# 1_ATmega_SoC_schdoc.net
KiCad netlist of a schematic drawn in Altium Designer
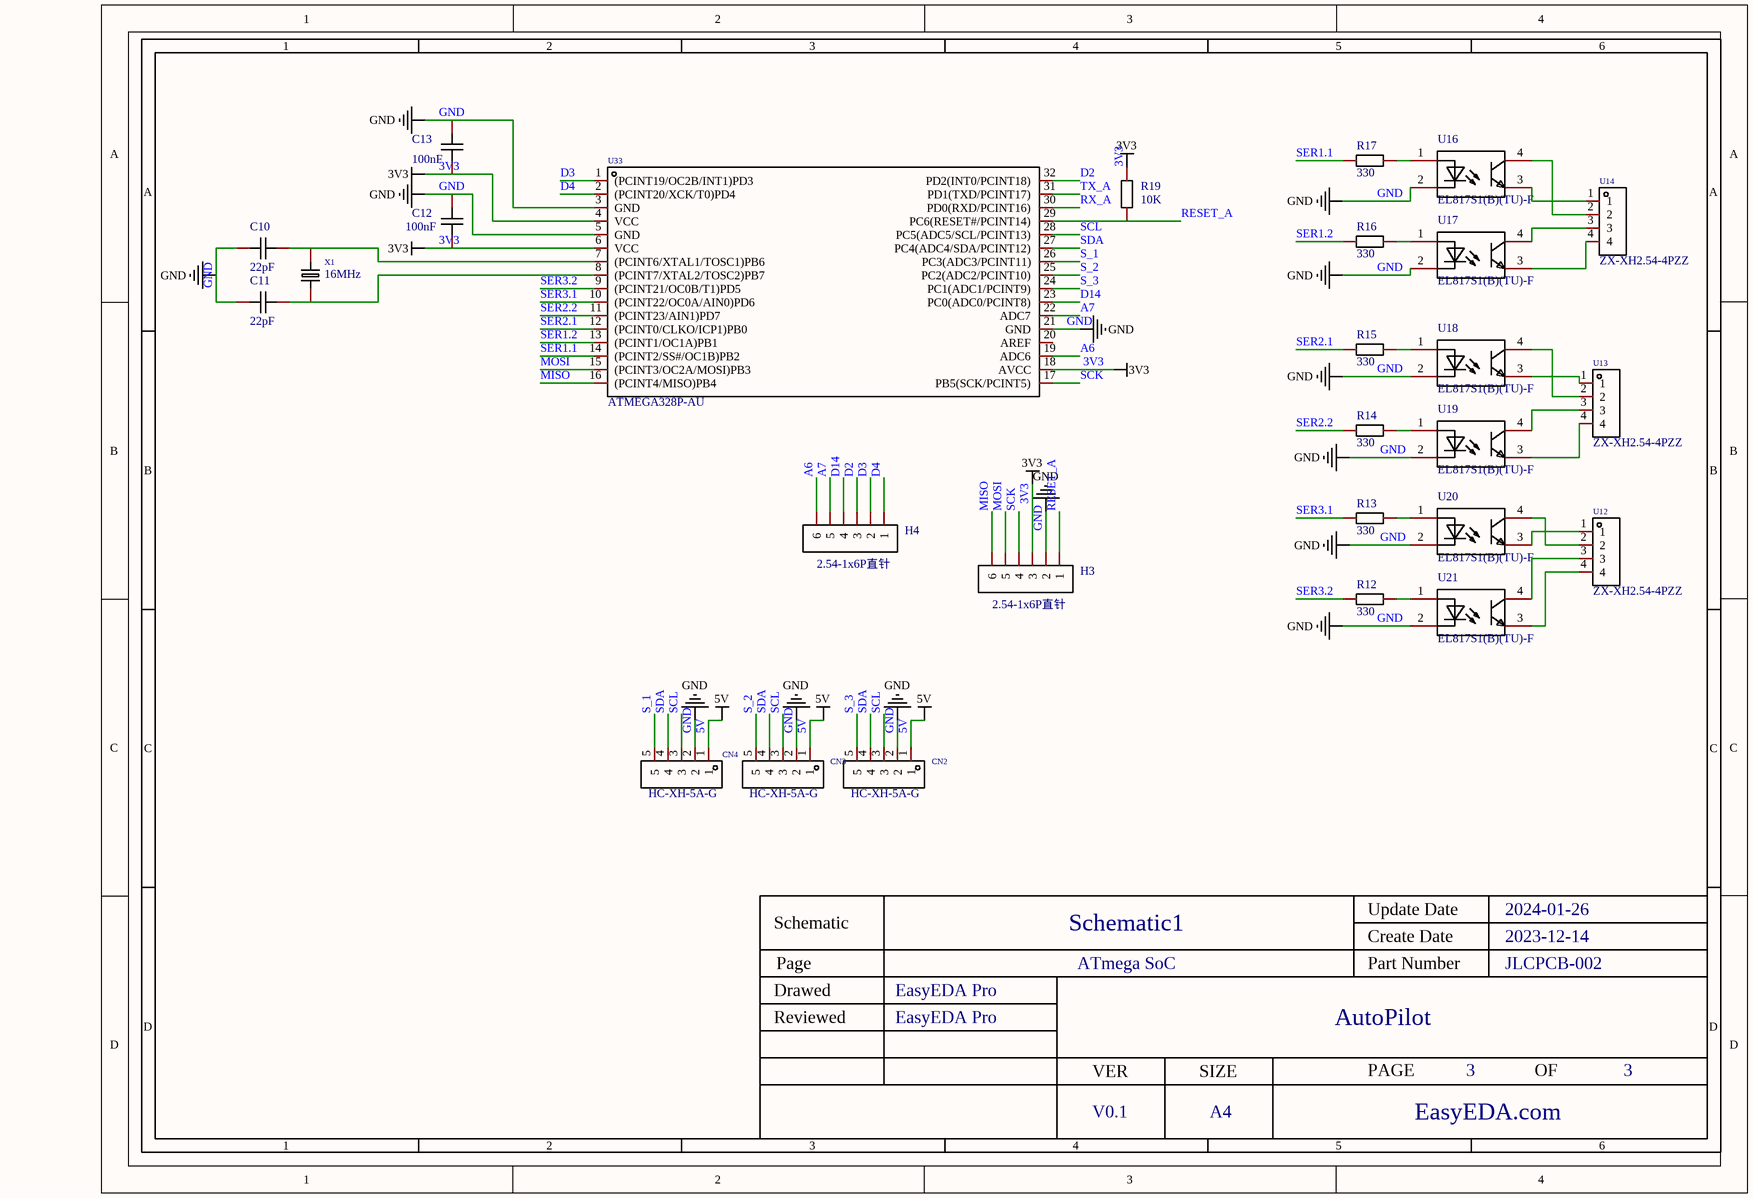
[diagram p0: 1_ATmega SoC.schdoc.schdoc]

(export (version "E")
  (design (tool "Eeschema 10.0.6"))
  (components
    (comp (ref "C10")
      (value "22pF")
      (fields (field (name "NAME") "22pF"))
      (libsource (lib "altium-import") (part "root_0_CAP_0603_"))
    )
    (comp (ref "C11")
      (value "22pF")
      (fields (field (name "NAME") "22pF"))
      (libsource (lib "altium-import") (part "root_0_CAP_0603_"))
    )
    (comp (ref "C12")
      (value "100nF")
      (fields (field (name "NAME") "100nF"))
      (libsource (lib "altium-import") (part "root_1_CAP_0603_"))
    )
    (comp (ref "C13")
      (value "100nF")
      (fields (field (name "NAME") "100nF"))
      (libsource (lib "altium-import") (part "root_1_CAP_0603_"))
    )
    (comp (ref "CN2")
      (value "HC-XH-5A-G")
      (fields (field (name "NAME") "HC-XH-5A-G") (field (name "MANUFACTURER") "HCTL(华灿天禄)"))
      (libsource (lib "altium-import") (part "root_3_HC-XH-5A-G_"))
    )
    (comp (ref "CN3")
      (value "HC-XH-5A-G")
      (fields (field (name "NAME") "HC-XH-5A-G") (field (name "MANUFACTURER") "HCTL(华灿天禄)"))
      (libsource (lib "altium-import") (part "root_3_HC-XH-5A-G_"))
    )
    (comp (ref "CN4")
      (value "HC-XH-5A-G")
      (fields (field (name "NAME") "HC-XH-5A-G") (field (name "MANUFACTURER") "HCTL(华灿天禄)"))
      (libsource (lib "altium-import") (part "root_3_HC-XH-5A-G_"))
    )
    (comp (ref "H3")
      (value "2.54-1x6P直针")
      (fields (field (name "NAME") "2.54-1x6P直针") (field (name "MANUFACTURER") "BOOMELE(博穆精密)"))
      (libsource (lib "altium-import") (part "root_3_2.54-1x6P直针_"))
    )
    (comp (ref "H4")
      (value "2.54-1x6P直针")
      (fields (field (name "NAME") "2.54-1x6P直针") (field (name "MANUFACTURER") "BOOMELE(博穆精密)"))
      (libsource (lib "altium-import") (part "root_3_2.54-1x6P直针_"))
    )
    (comp (ref "R12")
      (value "330")
      (fields (field (name "NAME") "330"))
      (libsource (lib "altium-import") (part "root_0_Res_0603_"))
    )
    (comp (ref "R13")
      (value "330")
      (fields (field (name "NAME") "330"))
      (libsource (lib "altium-import") (part "root_0_Res_0603_"))
    )
    (comp (ref "R14")
      (value "330")
      (fields (field (name "NAME") "330"))
      (libsource (lib "altium-import") (part "root_0_Res_0603_"))
    )
    (comp (ref "R15")
      (value "330")
      (fields (field (name "NAME") "330"))
      (libsource (lib "altium-import") (part "root_0_Res_0603_"))
    )
    (comp (ref "R16")
      (value "330")
      (fields (field (name "NAME") "330"))
      (libsource (lib "altium-import") (part "root_0_Res_0603_"))
    )
    (comp (ref "R17")
      (value "330")
      (fields (field (name "NAME") "330"))
      (libsource (lib "altium-import") (part "root_0_Res_0603_"))
    )
    (comp (ref "R19")
      (value "10K")
      (fields (field (name "NAME") "10K"))
      (libsource (lib "altium-import") (part "root_1_Res_0603_"))
    )
    (comp (ref "U12")
      (value "ZX-XH2.54-4PZZ")
      (fields (field (name "NAME") "ZX-XH2.54-4PZZ") (field (name "MANUFACTURER") "Megastar(兆星)"))
      (libsource (lib "altium-import") (part "root_0_ZX-XH2.54-4PZZ_"))
    )
    (comp (ref "U13")
      (value "ZX-XH2.54-4PZZ")
      (fields (field (name "NAME") "ZX-XH2.54-4PZZ") (field (name "MANUFACTURER") "Megastar(兆星)"))
      (libsource (lib "altium-import") (part "root_0_ZX-XH2.54-4PZZ_"))
    )
    (comp (ref "U14")
      (value "ZX-XH2.54-4PZZ")
      (fields (field (name "NAME") "ZX-XH2.54-4PZZ") (field (name "MANUFACTURER") "Megastar(兆星)"))
      (libsource (lib "altium-import") (part "root_0_ZX-XH2.54-4PZZ_"))
    )
    (comp (ref "U16")
      (value "EL817S1(B)(TU)-F")
      (fields (field (name "NAME") "EL817S1(B)(TU)-F") (field (name "MANUFACTURER") "EVERLIGHT(亿光)"))
      (libsource (lib "altium-import") (part "root_0_EL817S1(B)(TU)-F_"))
    )
    (comp (ref "U17")
      (value "EL817S1(B)(TU)-F")
      (fields (field (name "NAME") "EL817S1(B)(TU)-F") (field (name "MANUFACTURER") "EVERLIGHT(亿光)"))
      (libsource (lib "altium-import") (part "root_0_EL817S1(B)(TU)-F_"))
    )
    (comp (ref "U18")
      (value "EL817S1(B)(TU)-F")
      (fields (field (name "NAME") "EL817S1(B)(TU)-F") (field (name "MANUFACTURER") "EVERLIGHT(亿光)"))
      (libsource (lib "altium-import") (part "root_0_EL817S1(B)(TU)-F_"))
    )
    (comp (ref "U19")
      (value "EL817S1(B)(TU)-F")
      (fields (field (name "NAME") "EL817S1(B)(TU)-F") (field (name "MANUFACTURER") "EVERLIGHT(亿光)"))
      (libsource (lib "altium-import") (part "root_0_EL817S1(B)(TU)-F_"))
    )
    (comp (ref "U20")
      (value "EL817S1(B)(TU)-F")
      (fields (field (name "NAME") "EL817S1(B)(TU)-F") (field (name "MANUFACTURER") "EVERLIGHT(亿光)"))
      (libsource (lib "altium-import") (part "root_0_EL817S1(B)(TU)-F_"))
    )
    (comp (ref "U21")
      (value "EL817S1(B)(TU)-F")
      (fields (field (name "NAME") "EL817S1(B)(TU)-F") (field (name "MANUFACTURER") "EVERLIGHT(亿光)"))
      (libsource (lib "altium-import") (part "root_0_EL817S1(B)(TU)-F_"))
    )
    (comp (ref "U33")
      (value "ATMEGA328P-AU")
      (fields (field (name "NAME") "ATMEGA328P-AU") (field (name "MANUFACTURER") "MICROCHIP(美国微芯)"))
      (libsource (lib "altium-import") (part "root_0_ATMEGA328P-AU_C14877_"))
    )
    (comp (ref "X1")
      (value "16MHz")
      (fields
        (field (name "NAME") "16MHz")
        (field (name "MANUFACTURER") "YJX(雅晶鑫)")
        (field (name "MANUFACTURER PART") "TAXM16M2GLFBET2T")
      )
      (libsource (lib "altium-import") (part "root_1_TAXM16M2GLFBET2T_"))
    )
  )
  (nets
    (net (code "1") (name "/A6") (class "Default")
      (node (ref "H4") (pin "6") (pinfunction "6_6") (pintype "passive"))
      (node (ref "U33") (pin "19") (pinfunction "ADC6_19") (pintype "passive"))
    )
    (net (code "2") (name "/A7") (class "Default")
      (node (ref "H4") (pin "5") (pinfunction "5_5") (pintype "passive"))
      (node (ref "U33") (pin "22") (pinfunction "ADC7_22") (pintype "passive"))
    )
    (net (code "3") (name "/D2") (class "Default")
      (node (ref "H4") (pin "3") (pinfunction "3_3") (pintype "passive"))
      (node (ref "U33") (pin "32") (pinfunction "PD2(INT0/PCINT18)_32") (pintype "passive"))
    )
    (net (code "4") (name "/D3") (class "Default")
      (node (ref "H4") (pin "2") (pinfunction "2_2") (pintype "passive"))
      (node (ref "U33") (pin "1") (pinfunction "(PCINT19/OC2B/INT1)PD3_1") (pintype "passive"))
    )
    (net (code "5") (name "/D4") (class "Default")
      (node (ref "H4") (pin "1") (pinfunction "1_1") (pintype "passive"))
      (node (ref "U33") (pin "2") (pinfunction "(PCINT20/XCK/T0)PD4_2") (pintype "passive"))
    )
    (net (code "6") (name "/D14") (class "Default")
      (node (ref "H4") (pin "4") (pinfunction "4_4") (pintype "passive"))
      (node (ref "U33") (pin "23") (pinfunction "PC0(ADC0/PCINT8)_23") (pintype "passive"))
    )
    (net (code "7") (name "/MISO") (class "Default")
      (node (ref "H3") (pin "6") (pinfunction "6_6") (pintype "passive"))
      (node (ref "U33") (pin "16") (pinfunction "(PCINT4/MISO)PB4_16") (pintype "passive"))
    )
    (net (code "8") (name "/MOSI") (class "Default")
      (node (ref "H3") (pin "5") (pinfunction "5_5") (pintype "passive"))
      (node (ref "U33") (pin "15") (pinfunction "(PCINT3/OC2A/MOSI)PB3_15") (pintype "passive"))
    )
    (net (code "9") (name "/RESET_A") (class "Default")
      (node (ref "H3") (pin "1") (pinfunction "1_1") (pintype "passive"))
      (node (ref "R19") (pin "1") (pinfunction "1_1") (pintype "passive"))
      (node (ref "U33") (pin "29") (pinfunction "PC6(RESET#/PCINT14)_29") (pintype "passive"))
    )
    (net (code "10") (name "/RX_A") (class "Default")
      (node (ref "U33") (pin "30") (pinfunction "PD0(RXD/PCINT16)_30") (pintype "passive"))
    )
    (net (code "11") (name "/SCK") (class "Default")
      (node (ref "H3") (pin "4") (pinfunction "4_4") (pintype "passive"))
      (node (ref "U33") (pin "17") (pinfunction "PB5(SCK/PCINT5)_17") (pintype "passive"))
    )
    (net (code "12") (name "/SCL") (class "Default")
      (node (ref "CN2") (pin "3") (pinfunction "3_3") (pintype "passive"))
      (node (ref "CN3") (pin "3") (pinfunction "3_3") (pintype "passive"))
      (node (ref "CN4") (pin "3") (pinfunction "3_3") (pintype "passive"))
      (node (ref "U33") (pin "28") (pinfunction "PC5(ADC5/SCL/PCINT13)_28") (pintype "passive"))
    )
    (net (code "13") (name "/SDA") (class "Default")
      (node (ref "CN2") (pin "4") (pinfunction "4_4") (pintype "passive"))
      (node (ref "CN3") (pin "4") (pinfunction "4_4") (pintype "passive"))
      (node (ref "CN4") (pin "4") (pinfunction "4_4") (pintype "passive"))
      (node (ref "U33") (pin "27") (pinfunction "PC4(ADC4/SDA/PCINT12)_27") (pintype "passive"))
    )
    (net (code "14") (name "/SER1.1") (class "Default")
      (node (ref "R17") (pin "1") (pinfunction "1_1") (pintype "passive"))
      (node (ref "U33") (pin "14") (pinfunction "(PCINT2/SS#/OC1B)PB2_14") (pintype "passive"))
    )
    (net (code "15") (name "/SER1.2") (class "Default")
      (node (ref "R16") (pin "1") (pinfunction "1_1") (pintype "passive"))
      (node (ref "U33") (pin "13") (pinfunction "(PCINT1/OC1A)PB1_13") (pintype "passive"))
    )
    (net (code "16") (name "/SER2.1") (class "Default")
      (node (ref "R15") (pin "1") (pinfunction "1_1") (pintype "passive"))
      (node (ref "U33") (pin "12") (pinfunction "(PCINT0/CLKO/ICP1)PB0_12") (pintype "passive"))
    )
    (net (code "17") (name "/SER2.2") (class "Default")
      (node (ref "R14") (pin "1") (pinfunction "1_1") (pintype "passive"))
      (node (ref "U33") (pin "11") (pinfunction "(PCINT23/AIN1)PD7_11") (pintype "passive"))
    )
    (net (code "18") (name "/SER3.1") (class "Default")
      (node (ref "R13") (pin "1") (pinfunction "1_1") (pintype "passive"))
      (node (ref "U33") (pin "10") (pinfunction "(PCINT22/OC0A/AIN0)PD6_10") (pintype "passive"))
    )
    (net (code "19") (name "/SER3.2") (class "Default")
      (node (ref "R12") (pin "1") (pinfunction "1_1") (pintype "passive"))
      (node (ref "U33") (pin "9") (pinfunction "(PCINT21/OC0B/T1)PD5_9") (pintype "passive"))
    )
    (net (code "20") (name "/S_1") (class "Default")
      (node (ref "CN4") (pin "5") (pinfunction "5_5") (pintype "passive"))
      (node (ref "U33") (pin "26") (pinfunction "PC3(ADC3/PCINT11)_26") (pintype "passive"))
    )
    (net (code "21") (name "/S_2") (class "Default")
      (node (ref "CN3") (pin "5") (pinfunction "5_5") (pintype "passive"))
      (node (ref "U33") (pin "25") (pinfunction "PC2(ADC2/PCINT10)_25") (pintype "passive"))
    )
    (net (code "22") (name "/S_3") (class "Default")
      (node (ref "CN2") (pin "5") (pinfunction "5_5") (pintype "passive"))
      (node (ref "U33") (pin "24") (pinfunction "PC1(ADC1/PCINT9)_24") (pintype "passive"))
    )
    (net (code "23") (name "/TX_A") (class "Default")
      (node (ref "U33") (pin "31") (pinfunction "PD1(TXD/PCINT17)_31") (pintype "passive"))
    )
    (net (code "24") (name "3V3") (class "Default")
      (node (ref "C12") (pin "2") (pinfunction "2_2") (pintype "passive"))
      (node (ref "C13") (pin "2") (pinfunction "2_2") (pintype "passive"))
      (node (ref "H3") (pin "3") (pinfunction "3_3") (pintype "passive"))
      (node (ref "R19") (pin "2") (pinfunction "2_2") (pintype "passive"))
      (node (ref "U33") (pin "18") (pinfunction "AVCC_18") (pintype "passive"))
      (node (ref "U33") (pin "4") (pinfunction "VCC_4") (pintype "passive"))
      (node (ref "U33") (pin "6") (pinfunction "VCC_6") (pintype "passive"))
    )
    (net (code "25") (name "5V") (class "Default")
      (node (ref "CN2") (pin "1") (pinfunction "1_1") (pintype "passive"))
      (node (ref "CN3") (pin "1") (pinfunction "1_1") (pintype "passive"))
      (node (ref "CN4") (pin "1") (pinfunction "1_1") (pintype "passive"))
    )
    (net (code "26") (name "GND") (class "Default")
      (node (ref "C10") (pin "2") (pinfunction "2_2") (pintype "passive"))
      (node (ref "C11") (pin "2") (pinfunction "2_2") (pintype "passive"))
      (node (ref "C12") (pin "1") (pinfunction "1_1") (pintype "passive"))
      (node (ref "C13") (pin "1") (pinfunction "1_1") (pintype "passive"))
      (node (ref "CN2") (pin "2") (pinfunction "2_2") (pintype "passive"))
      (node (ref "CN3") (pin "2") (pinfunction "2_2") (pintype "passive"))
      (node (ref "CN4") (pin "2") (pinfunction "2_2") (pintype "passive"))
      (node (ref "H3") (pin "2") (pinfunction "2_2") (pintype "passive"))
      (node (ref "U16") (pin "2") (pinfunction "CAT_2") (pintype "passive"))
      (node (ref "U17") (pin "2") (pinfunction "CAT_2") (pintype "passive"))
      (node (ref "U18") (pin "2") (pinfunction "CAT_2") (pintype "passive"))
      (node (ref "U19") (pin "2") (pinfunction "CAT_2") (pintype "passive"))
      (node (ref "U20") (pin "2") (pinfunction "CAT_2") (pintype "passive"))
      (node (ref "U21") (pin "2") (pinfunction "CAT_2") (pintype "passive"))
      (node (ref "U33") (pin "21") (pinfunction "GND_21") (pintype "passive"))
      (node (ref "U33") (pin "3") (pinfunction "GND_3") (pintype "passive"))
      (node (ref "U33") (pin "5") (pinfunction "GND_5") (pintype "passive"))
    )
    (net (code "27") (name "Net-(U16-AN)") (class "Default")
      (node (ref "R17") (pin "2") (pinfunction "2_2") (pintype "passive"))
      (node (ref "U16") (pin "1") (pinfunction "AN_1") (pintype "passive"))
    )
    (net (code "28") (name "Net-(U16-COL)") (class "Default")
      (node (ref "U14") (pin "2") (pinfunction "2_2") (pintype "passive"))
      (node (ref "U16") (pin "4") (pinfunction "COL_4") (pintype "passive"))
    )
    (net (code "29") (name "Net-(U16-EM)") (class "Default")
      (node (ref "U14") (pin "1") (pinfunction "1_1") (pintype "passive"))
      (node (ref "U16") (pin "3") (pinfunction "EM_3") (pintype "passive"))
    )
    (net (code "30") (name "Net-(U17-AN)") (class "Default")
      (node (ref "R16") (pin "2") (pinfunction "2_2") (pintype "passive"))
      (node (ref "U17") (pin "1") (pinfunction "AN_1") (pintype "passive"))
    )
    (net (code "31") (name "Net-(U17-COL)") (class "Default")
      (node (ref "U14") (pin "3") (pinfunction "3_3") (pintype "passive"))
      (node (ref "U17") (pin "4") (pinfunction "COL_4") (pintype "passive"))
    )
    (net (code "32") (name "Net-(U17-EM)") (class "Default")
      (node (ref "U14") (pin "4") (pinfunction "4_4") (pintype "passive"))
      (node (ref "U17") (pin "3") (pinfunction "EM_3") (pintype "passive"))
    )
    (net (code "33") (name "Net-(U18-AN)") (class "Default")
      (node (ref "R15") (pin "2") (pinfunction "2_2") (pintype "passive"))
      (node (ref "U18") (pin "1") (pinfunction "AN_1") (pintype "passive"))
    )
    (net (code "34") (name "Net-(U18-COL)") (class "Default")
      (node (ref "U13") (pin "2") (pinfunction "2_2") (pintype "passive"))
      (node (ref "U18") (pin "4") (pinfunction "COL_4") (pintype "passive"))
    )
    (net (code "35") (name "Net-(U18-EM)") (class "Default")
      (node (ref "U13") (pin "1") (pinfunction "1_1") (pintype "passive"))
      (node (ref "U18") (pin "3") (pinfunction "EM_3") (pintype "passive"))
    )
    (net (code "36") (name "Net-(U19-AN)") (class "Default")
      (node (ref "R14") (pin "2") (pinfunction "2_2") (pintype "passive"))
      (node (ref "U19") (pin "1") (pinfunction "AN_1") (pintype "passive"))
    )
    (net (code "37") (name "Net-(U19-COL)") (class "Default")
      (node (ref "U13") (pin "3") (pinfunction "3_3") (pintype "passive"))
      (node (ref "U19") (pin "4") (pinfunction "COL_4") (pintype "passive"))
    )
    (net (code "38") (name "Net-(U19-EM)") (class "Default")
      (node (ref "U13") (pin "4") (pinfunction "4_4") (pintype "passive"))
      (node (ref "U19") (pin "3") (pinfunction "EM_3") (pintype "passive"))
    )
    (net (code "39") (name "Net-(U20-AN)") (class "Default")
      (node (ref "R13") (pin "2") (pinfunction "2_2") (pintype "passive"))
      (node (ref "U20") (pin "1") (pinfunction "AN_1") (pintype "passive"))
    )
    (net (code "40") (name "Net-(U20-COL)") (class "Default")
      (node (ref "U12") (pin "2") (pinfunction "2_2") (pintype "passive"))
      (node (ref "U20") (pin "4") (pinfunction "COL_4") (pintype "passive"))
    )
    (net (code "41") (name "Net-(U20-EM)") (class "Default")
      (node (ref "U12") (pin "1") (pinfunction "1_1") (pintype "passive"))
      (node (ref "U20") (pin "3") (pinfunction "EM_3") (pintype "passive"))
    )
    (net (code "42") (name "Net-(U21-AN)") (class "Default")
      (node (ref "R12") (pin "2") (pinfunction "2_2") (pintype "passive"))
      (node (ref "U21") (pin "1") (pinfunction "AN_1") (pintype "passive"))
    )
    (net (code "43") (name "Net-(U21-COL)") (class "Default")
      (node (ref "U12") (pin "3") (pinfunction "3_3") (pintype "passive"))
      (node (ref "U21") (pin "4") (pinfunction "COL_4") (pintype "passive"))
    )
    (net (code "44") (name "Net-(U21-EM)") (class "Default")
      (node (ref "U12") (pin "4") (pinfunction "4_4") (pintype "passive"))
      (node (ref "U21") (pin "3") (pinfunction "EM_3") (pintype "passive"))
    )
    (net (code "45") (name "Net-(U33-(PCINT6{slash}XTAL1{slash}TOSC1)PB6)") (class "Default")
      (node (ref "C10") (pin "1") (pinfunction "1_1") (pintype "passive"))
      (node (ref "U33") (pin "7") (pinfunction "(PCINT6/XTAL1/TOSC1)PB6_7") (pintype "passive"))
      (node (ref "X1") (pin "2") (pinfunction "2_2") (pintype "passive"))
    )
    (net (code "46") (name "Net-(U33-(PCINT7{slash}XTAL2{slash}TOSC2)PB7)") (class "Default")
      (node (ref "C11") (pin "1") (pinfunction "1_1") (pintype "passive"))
      (node (ref "U33") (pin "8") (pinfunction "(PCINT7/XTAL2/TOSC2)PB7_8") (pintype "passive"))
      (node (ref "X1") (pin "1") (pinfunction "1_1") (pintype "passive"))
    )
    (net (code "47") (name "unconnected-(U33-AREF-Pad20)") (class "Default")
      (node (ref "U33") (pin "20") (pinfunction "AREF_20") (pintype "passive"))
    )
  )
)
